# Front_right_lamp_v4B.net
KiCad netlist of a schematic drawn in EAGLE
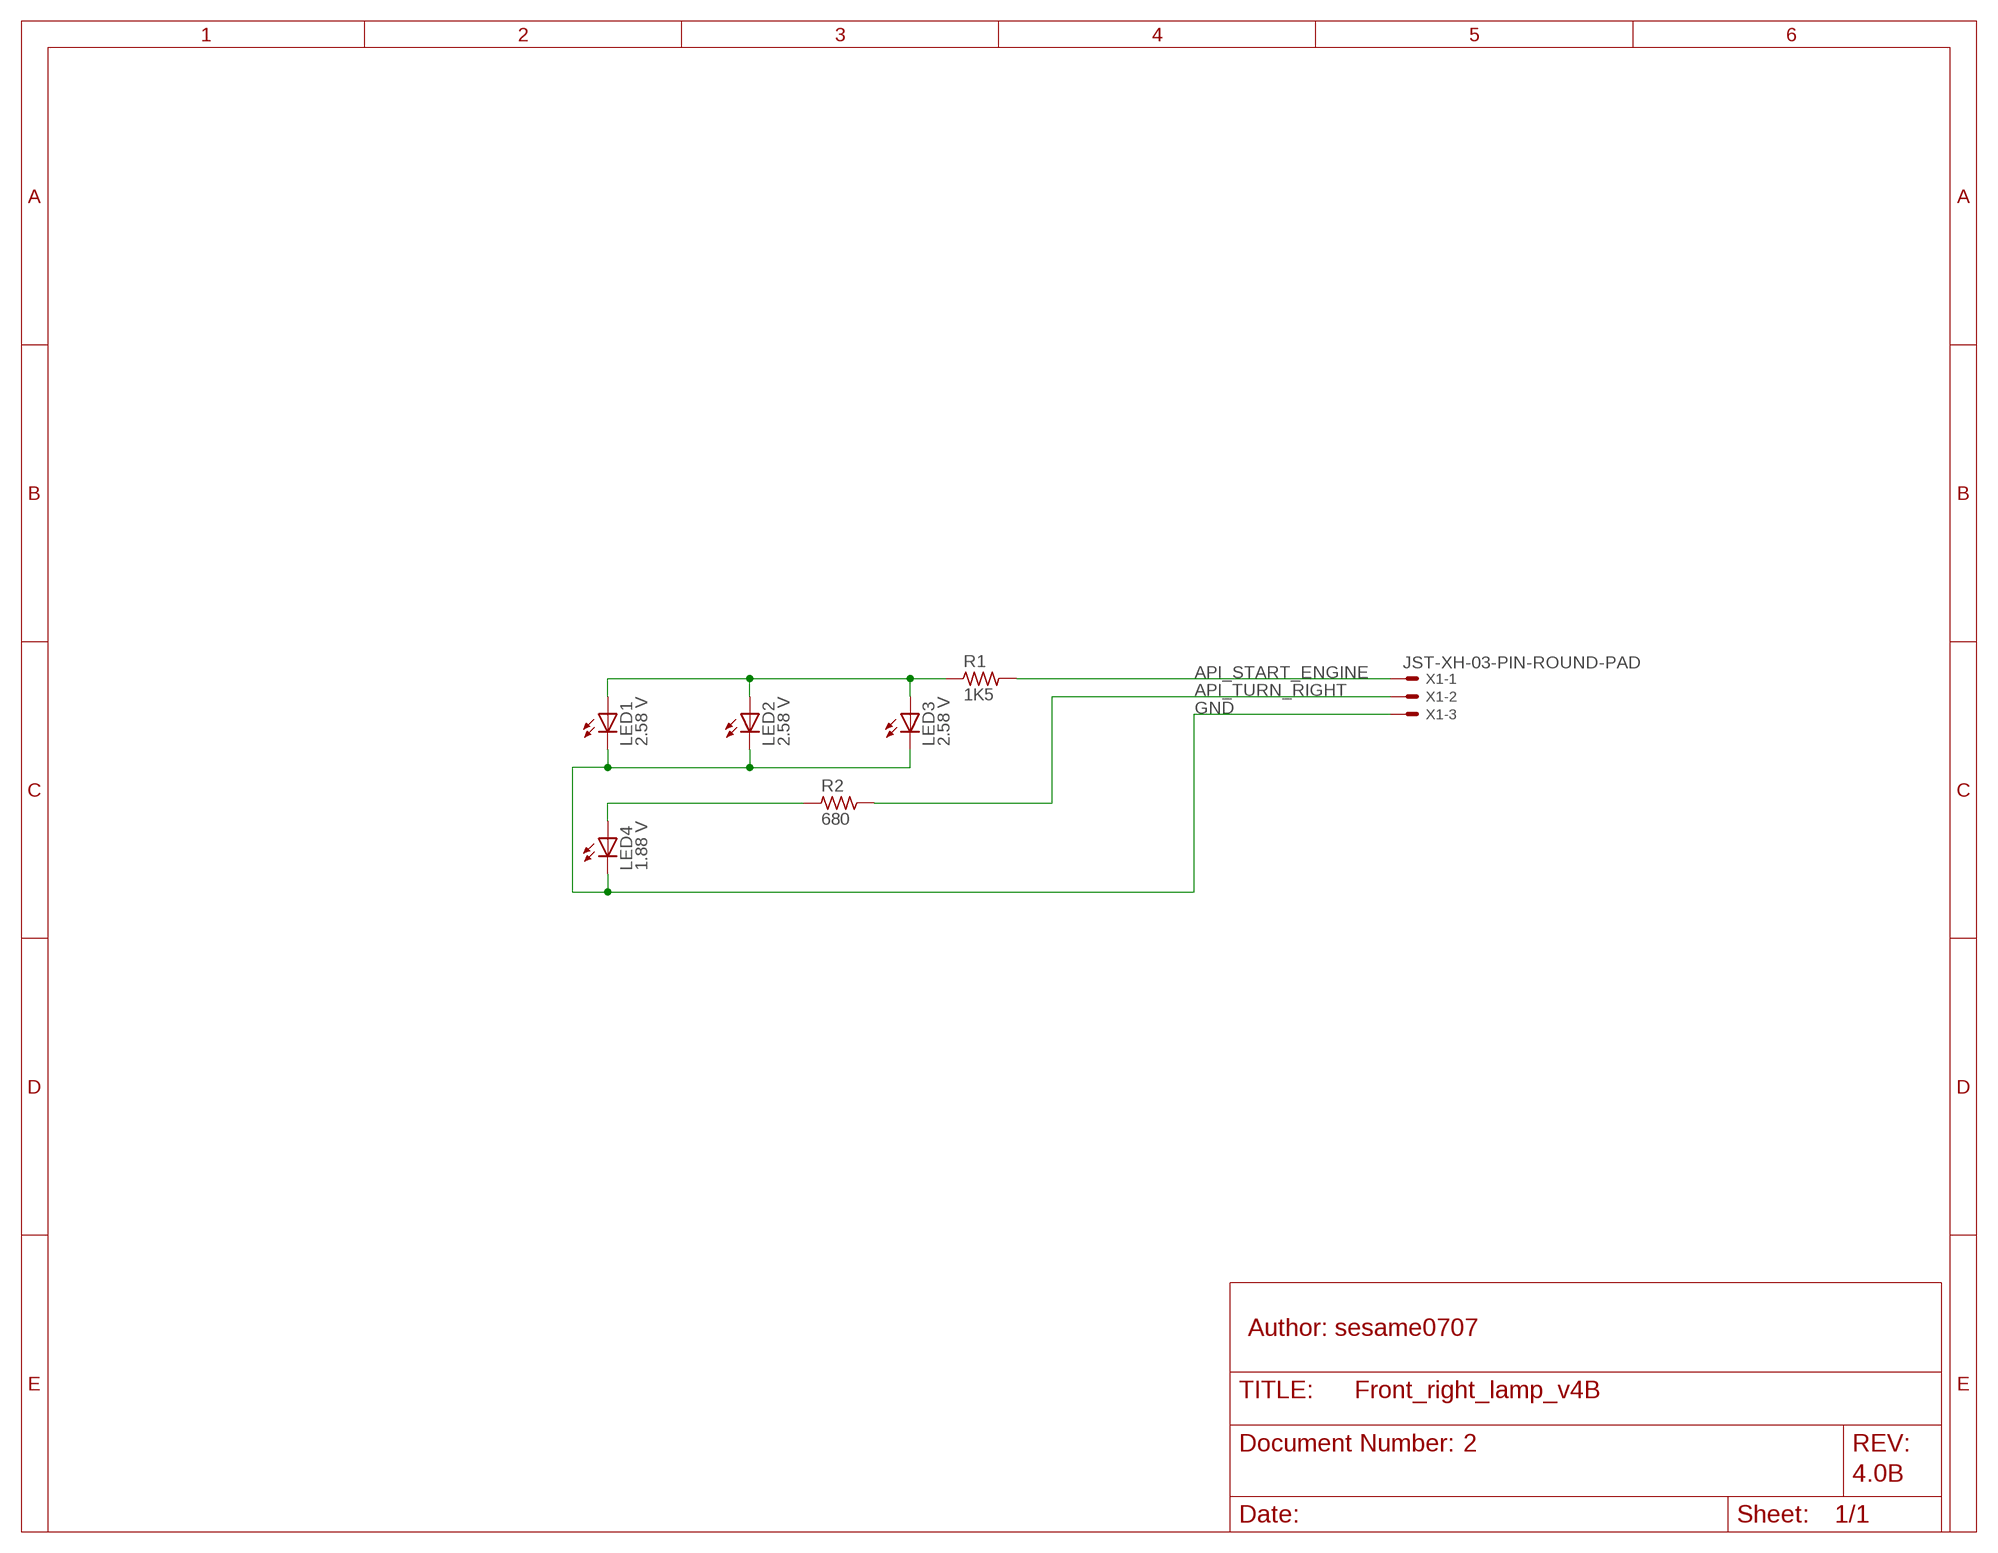
[diagram p0: schematic, sheet 1]

(export (version "E")
  (design (tool "Eeschema 10.0.6"))
  (components
    (comp (ref "LED1")
      (value "2.58 V")
      (footprint "eagle-import:LED5MM")
      (libsource (lib "eagle-import") (part "LED5MM"))
    )
    (comp (ref "LED2")
      (value "2.58 V")
      (footprint "eagle-import:LED5MM")
      (libsource (lib "eagle-import") (part "LED5MM"))
    )
    (comp (ref "LED3")
      (value "2.58 V")
      (footprint "eagle-import:LED5MM")
      (libsource (lib "eagle-import") (part "LED5MM"))
    )
    (comp (ref "LED4")
      (value "1.88 V")
      (footprint "eagle-import:LED5MM")
      (libsource (lib "eagle-import") (part "LED5MM"))
    )
    (comp (ref "R1")
      (value "1K5")
      (footprint "eagle-import:R1206")
      (libsource (lib "eagle-import") (part "R_1206"))
    )
    (comp (ref "R2")
      (value "680")
      (footprint "eagle-import:R1206")
      (libsource (lib "eagle-import") (part "R_1206"))
    )
    (comp (ref "X1")
      (value "JST-XH-03-PIN-ROUND-PAD")
      (footprint "eagle-import:JST-XH-03-PACKAGE-ROUND-PAD")
      (libsource (lib "eagle-import") (part "JST-XH-03-PIN-ROUND-PAD"))
    )
  )
  (nets
    (net (code "1") (name "/API_START_ENGINE") (class "Default")
      (node (ref "LED1") (pin "A") (pinfunction "A_A") (pintype "passive"))
      (node (ref "LED2") (pin "A") (pinfunction "A_A") (pintype "passive"))
      (node (ref "LED3") (pin "A") (pinfunction "A_A") (pintype "passive"))
      (node (ref "R1") (pin "1") (pinfunction "1_1") (pintype "passive"))
    )
    (net (code "2") (name "/API_TURN_RIGHT") (class "Default")
      (node (ref "R2") (pin "2") (pinfunction "2_2") (pintype "passive"))
      (node (ref "X1") (pin "2") (pinfunction "S_2") (pintype "passive"))
    )
    (net (code "3") (name "/GND") (class "Default")
      (node (ref "LED1") (pin "K") (pinfunction "C_K") (pintype "passive"))
      (node (ref "LED2") (pin "K") (pinfunction "C_K") (pintype "passive"))
      (node (ref "LED3") (pin "K") (pinfunction "C_K") (pintype "passive"))
      (node (ref "LED4") (pin "K") (pinfunction "C_K") (pintype "passive"))
      (node (ref "X1") (pin "3") (pinfunction "S_3") (pintype "passive"))
    )
    (net (code "4") (name "Net-(LED4-PadA)") (class "Default")
      (node (ref "LED4") (pin "A") (pinfunction "A_A") (pintype "passive"))
      (node (ref "R2") (pin "1") (pinfunction "1_1") (pintype "passive"))
    )
    (net (code "5") (name "Net-(X1A-S)") (class "Default")
      (node (ref "R1") (pin "2") (pinfunction "2_2") (pintype "passive"))
      (node (ref "X1") (pin "1") (pinfunction "S_1") (pintype "passive"))
    )
  )
)
